# Potencia_Moway.net
KiCad netlist of a schematic drawn in Altium Designer
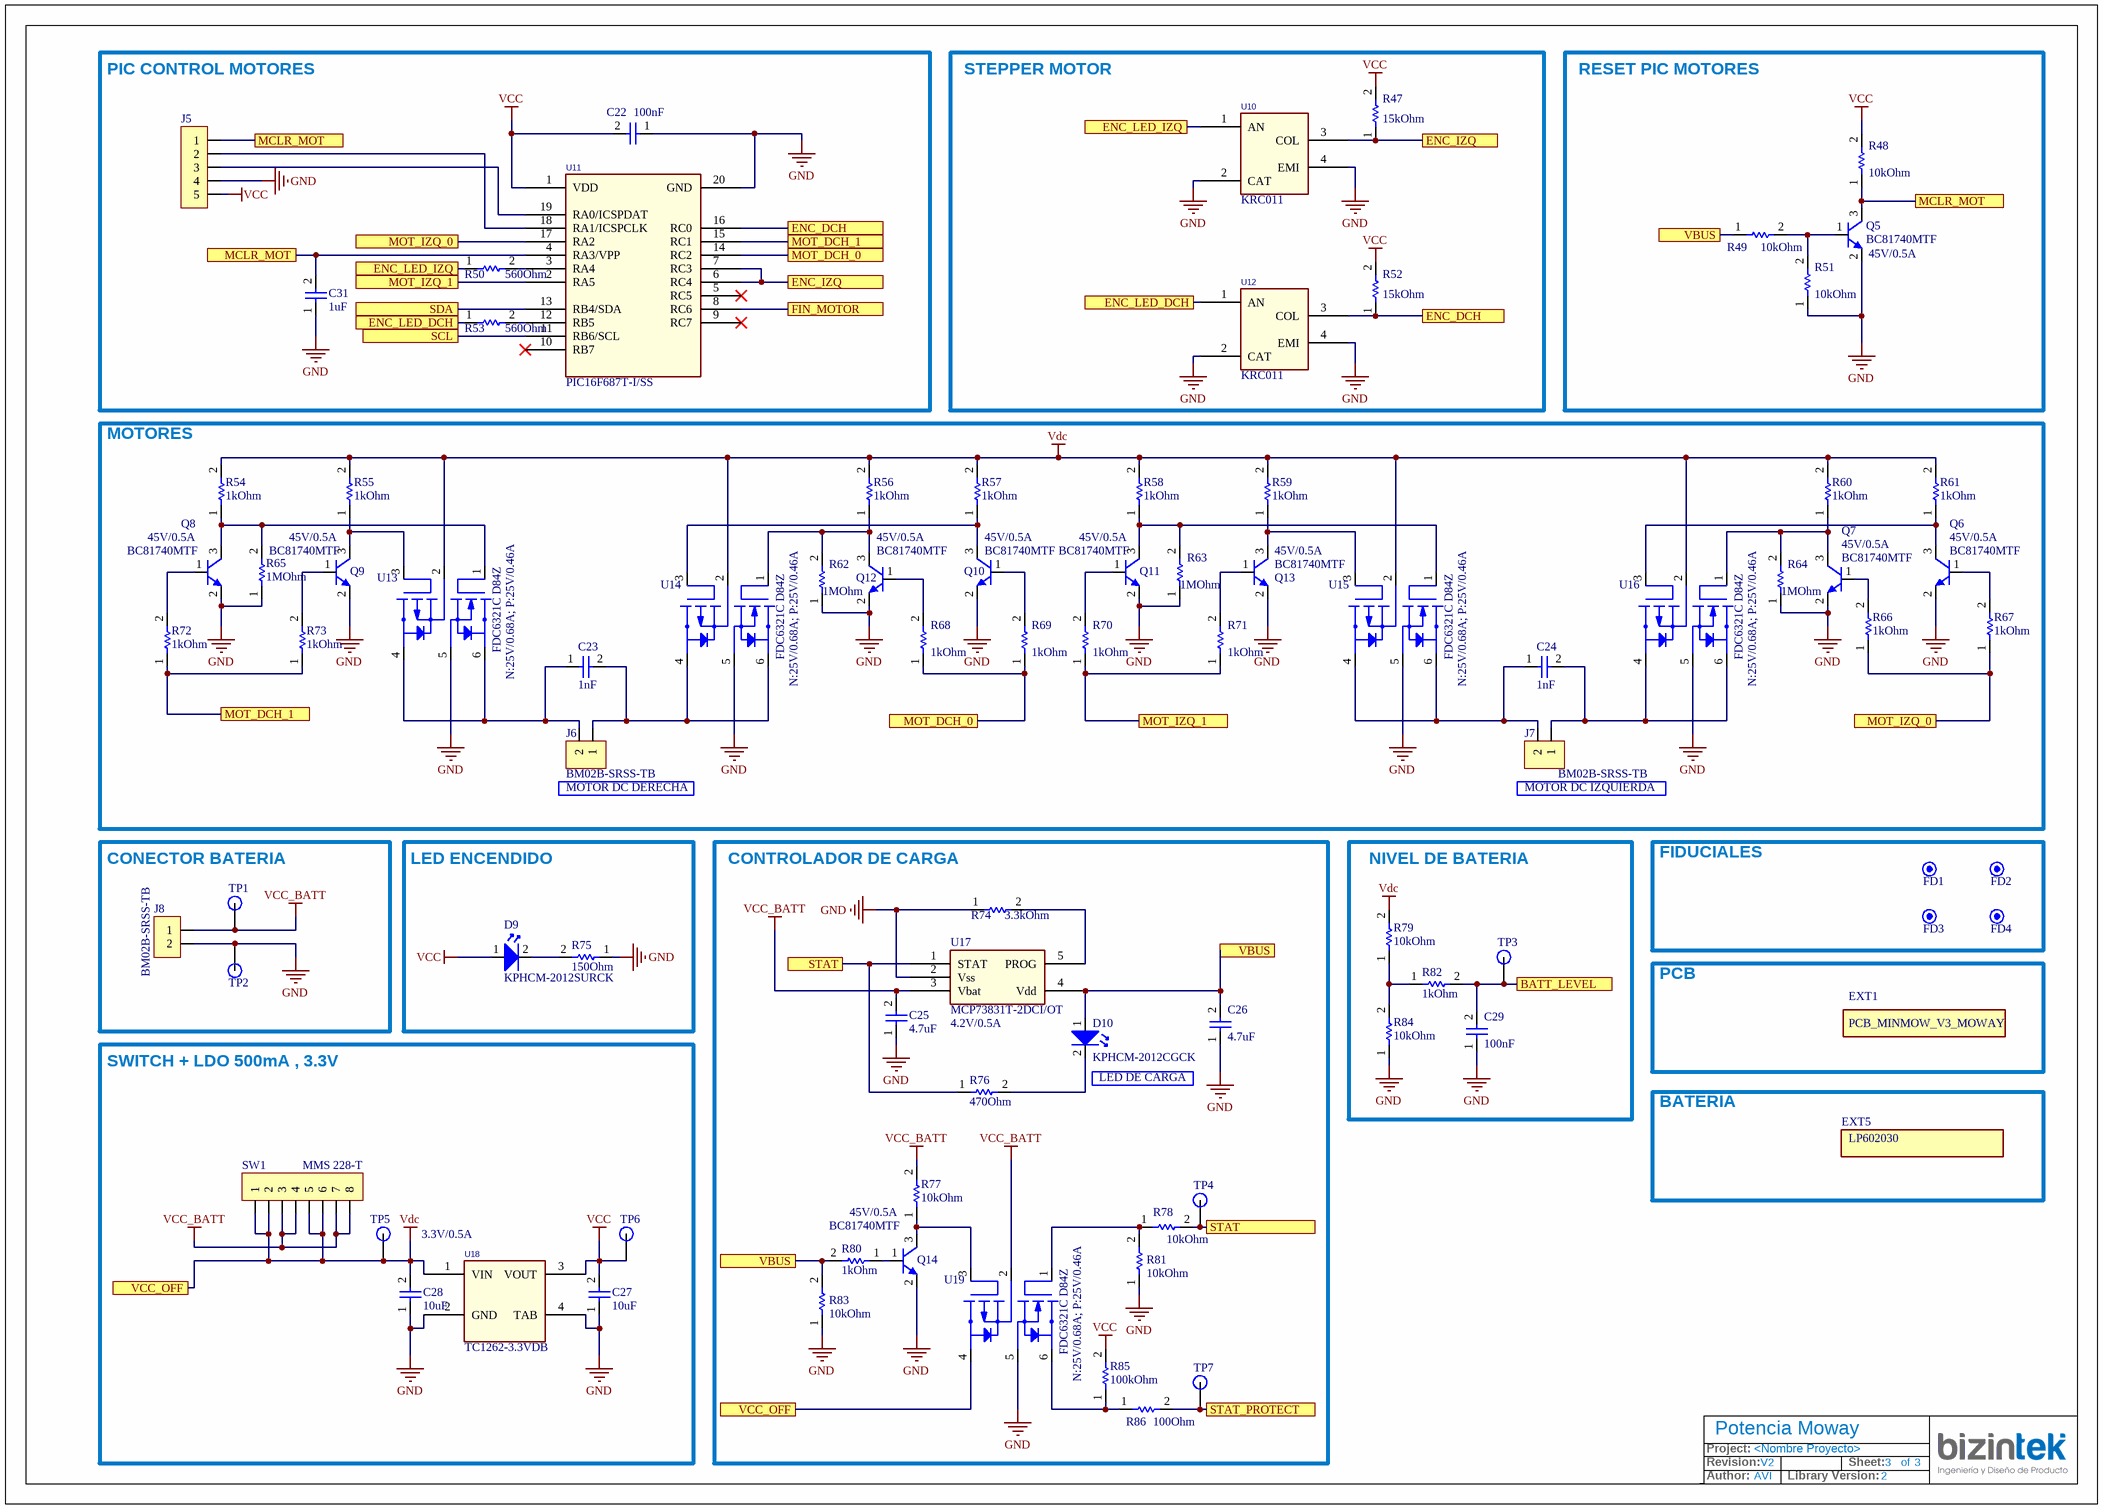
[diagram p0: Potencia_Moway.SchDoc]

(export (version "E")
  (design (tool "Eeschema 10.0.6"))
  (components
    (comp (ref "C22")
      (value "100nF")
      (footprint "C0402")
      (description "CAPACITOR SMD 0402, 100nF, 10V, X7R")
      (fields (field (name "PART NUMBER") "C100NV10X7R0402") (field (name "VOLTAGE") "10"))
      (libsource (lib "BZI_ALTIUMLIB") (part "CAPACITOR"))
    )
    (comp (ref "C23")
      (value "1nF")
      (footprint "C0402")
      (description "CAPACITOR SMD 0402, 1nF, 10V, X7R")
      (fields (field (name "PART NUMBER") "C1NV10X7R0402"))
      (libsource (lib "BZI_ALTIUMLIB") (part "CAPACITOR"))
    )
    (comp (ref "C24")
      (value "1nF")
      (footprint "C0402")
      (description "CAPACITOR SMD 0402, 1nF, 10V, X7R")
      (fields (field (name "PART NUMBER") "C1NV10X7R0402"))
      (libsource (lib "BZI_ALTIUMLIB") (part "CAPACITOR"))
    )
    (comp (ref "C25")
      (value "4.7uF")
      (footprint "C0402")
      (description "CAPACITOR SMD 0402, 4.7uF, 10V, X5R")
      (fields (field (name "PART NUMBER") "C4U7V10X5R0402") (field (name "VOLTAGE") "10"))
      (libsource (lib "BZI_ALTIUMLIB") (part "CAPACITOR"))
    )
    (comp (ref "C26")
      (value "4.7uF")
      (footprint "C0402")
      (description "CAPACITOR SMD 0402, 4.7uF, 10V, X5R")
      (fields (field (name "PART NUMBER") "C4U7V10X5R0402") (field (name "VOLTAGE") "10"))
      (libsource (lib "BZI_ALTIUMLIB") (part "CAPACITOR"))
    )
    (comp (ref "C27")
      (value "10uF")
      (footprint "C0603")
      (description "CAPACITOR SMD 0603, 10uF, 10V, X5R")
      (fields (field (name "PART NUMBER") "C10UV10X5R0603") (field (name "VOLTAGE") "10"))
      (libsource (lib "BZI_ALTIUMLIB") (part "CAPACITOR"))
    )
    (comp (ref "C28")
      (value "10uF")
      (footprint "C0603")
      (description "CAPACITOR SMD 0603, 10uF, 10V, X5R")
      (fields (field (name "PART NUMBER") "C10UV10X5R0603") (field (name "VOLTAGE") "10"))
      (libsource (lib "BZI_ALTIUMLIB") (part "CAPACITOR"))
    )
    (comp (ref "C29")
      (value "100nF")
      (footprint "C0402")
      (description "CAPACITOR SMD 0402, 100nF, 10V, X7R")
      (fields (field (name "PART NUMBER") "C100NV10X7R0402") (field (name "VOLTAGE") "10"))
      (libsource (lib "BZI_ALTIUMLIB") (part "CAPACITOR"))
    )
    (comp (ref "C31")
      (value "1uF")
      (footprint "C0402")
      (description "CAPACITOR SMD 0402, 1uF, 10V, X5R")
      (fields (field (name "PART NUMBER") "C1UV10X5R0402"))
      (libsource (lib "BZI_ALTIUMLIB") (part "CAPACITOR"))
    )
    (comp (ref "D9")
      (value "KPHCM2012SURCK")
      (footprint "LED0805")
      (description "LED, Low Power, Red, SMD, 20 mA, 1.95 V, 630 nm")
      (fields
        (field (name "MANUFACTURER PART NUMBER") "KPHCM-2012SURCK")
        (field (name "MANUFACTURER") "KINGBRIGHT")
      )
      (libsource (lib "BZI_ALTIUMLIB") (part "DIODE_LED"))
    )
    (comp (ref "D10")
      (value "KPHCM2012CGCK")
      (footprint "LED0805")
      (description "LED, Low Power, Green, SMD, 20 mA, 2.1 V, 570 nm")
      (fields
        (field (name "MANUFACTURER PART NUMBER") "KPHCM-2012CGCK")
        (field (name "MANUFACTURER") "KINGBRIGHT")
      )
      (libsource (lib "BZI_ALTIUMLIB") (part "DIODE_LED"))
    )
    (comp (ref "EXT1")
      (value "PCB_MINMOW_V3_MOWAY")
      (fields (field (name "PART NUMBER") "PCB") (field (name "MANUFACTURER") "BIZINTEK"))
      (libsource (lib "BZI_ALTIUMLIB") (part "EXTERNAL_GEN"))
    )
    (comp (ref "EXT5")
      (value "LP602030")
      (description "Li-Polymer Battery, 3.7V, 300mAh")
      (fields
        (field (name "MANUFACTURER PART NUMBER") "LP602030")
        (field (name "ALTIUM_VALUE") "3.7V/0.30Ah")
        (field (name "MANUFACTURER") "EEMB")
      )
      (libsource (lib "BZI_ALTIUMLIB") (part "EXTERNAL_GEN"))
    )
    (comp (ref "FD1")
      (value "FIDUCIAL")
      (footprint "FIDUCIAL")
      (libsource (lib "BZI_ALTIUMLIB") (part "FIDUCIAL"))
    )
    (comp (ref "FD2")
      (value "FIDUCIAL")
      (footprint "FIDUCIAL")
      (libsource (lib "BZI_ALTIUMLIB") (part "FIDUCIAL"))
    )
    (comp (ref "FD3")
      (value "FIDUCIAL")
      (footprint "FIDUCIAL")
      (libsource (lib "BZI_ALTIUMLIB") (part "FIDUCIAL"))
    )
    (comp (ref "FD4")
      (value "FIDUCIAL")
      (footprint "FIDUCIAL")
      (libsource (lib "BZI_ALTIUMLIB") (part "FIDUCIAL"))
    )
    (comp (ref "J5")
      (value "PAD_5PIN_TH_2X1MM_1.5MM_PITCH")
      (footprint "PAD_5PIN_TH_2X1MM_1.5MM_PITCH")
      (libsource (lib "BZI_ALTIUMLIB") (part "HEADER_5PIN"))
    )
    (comp (ref "J6")
      (value "BM02BSRSSTB")
      (footprint "BM02BSRSSTB_JST")
      (description "Wire-To-Board Connector, Top Entry, 1 mm, 2 Contacts, Header, SR Series, Surface Mount, 1 Rows")
      (fields (field (name "MANUFACTURER PART NUMBER") "BM02B-SRSS-TB") (field (name "MANUFACTURER") "JST"))
      (libsource (lib "BZI_ALTIUMLIB") (part "HEADER_2PIN"))
    )
    (comp (ref "J7")
      (value "BM02BSRSSTB")
      (footprint "BM02BSRSSTB_JST")
      (description "Wire-To-Board Connector, Top Entry, 1 mm, 2 Contacts, Header, SR Series, Surface Mount, 1 Rows")
      (fields (field (name "MANUFACTURER PART NUMBER") "BM02B-SRSS-TB") (field (name "MANUFACTURER") "JST"))
      (libsource (lib "BZI_ALTIUMLIB") (part "HEADER_2PIN"))
    )
    (comp (ref "J8")
      (value "BM02BSRSSTB")
      (footprint "BM02BSRSSTB_JST")
      (description "Wire-To-Board Connector, Top Entry, 1 mm, 2 Contacts, Header, SR Series, Surface Mount, 1 Rows")
      (fields (field (name "MANUFACTURER PART NUMBER") "BM02B-SRSS-TB") (field (name "MANUFACTURER") "JST"))
      (libsource (lib "BZI_ALTIUMLIB") (part "HEADER_2PIN"))
    )
    (comp (ref "Q5")
      (value "45V/0.5A")
      (footprint "SOT23_FAIRCHILD")
      (description "Bipolar (BJT) Single Transistor, NPN, 45 V, 170 MHz, 300 mW, 500 mA, 250 hFE")
      (fields
        (field (name "PART NUMBER") "BC81740MTF")
        (field (name "MANUFACTURER PART NUMBER") "BC81740MTF")
        (field (name "MANUFACTURER") "FAIRCHILD")
      )
      (libsource (lib "BZI_ALTIUMLIB") (part "BJT_NPN"))
    )
    (comp (ref "Q6")
      (value "45V/0.5A")
      (footprint "SOT23_FAIRCHILD")
      (description "Bipolar (BJT) Single Transistor, NPN, 45 V, 170 MHz, 300 mW, 500 mA, 250 hFE")
      (fields
        (field (name "PART NUMBER") "BC81740MTF")
        (field (name "MANUFACTURER PART NUMBER") "BC81740MTF")
        (field (name "MANUFACTURER") "FAIRCHILD")
      )
      (libsource (lib "BZI_ALTIUMLIB") (part "BJT_NPN"))
    )
    (comp (ref "Q7")
      (value "45V/0.5A")
      (footprint "SOT23_FAIRCHILD")
      (description "Bipolar (BJT) Single Transistor, NPN, 45 V, 170 MHz, 300 mW, 500 mA, 250 hFE")
      (fields
        (field (name "PART NUMBER") "BC81740MTF")
        (field (name "MANUFACTURER PART NUMBER") "BC81740MTF")
        (field (name "MANUFACTURER") "FAIRCHILD")
      )
      (libsource (lib "BZI_ALTIUMLIB") (part "BJT_NPN"))
    )
    (comp (ref "Q8")
      (value "45V/0.5A")
      (footprint "SOT23_FAIRCHILD")
      (description "Bipolar (BJT) Single Transistor, NPN, 45 V, 170 MHz, 300 mW, 500 mA, 250 hFE")
      (fields
        (field (name "PART NUMBER") "BC81740MTF")
        (field (name "MANUFACTURER PART NUMBER") "BC81740MTF")
        (field (name "MANUFACTURER") "FAIRCHILD")
      )
      (libsource (lib "BZI_ALTIUMLIB") (part "BJT_NPN"))
    )
    (comp (ref "Q9")
      (value "45V/0.5A")
      (footprint "SOT23_FAIRCHILD")
      (description "Bipolar (BJT) Single Transistor, NPN, 45 V, 170 MHz, 300 mW, 500 mA, 250 hFE")
      (fields
        (field (name "PART NUMBER") "BC81740MTF")
        (field (name "MANUFACTURER PART NUMBER") "BC81740MTF")
        (field (name "MANUFACTURER") "FAIRCHILD")
      )
      (libsource (lib "BZI_ALTIUMLIB") (part "BJT_NPN"))
    )
    (comp (ref "Q10")
      (value "45V/0.5A")
      (footprint "SOT23_FAIRCHILD")
      (description "Bipolar (BJT) Single Transistor, NPN, 45 V, 170 MHz, 300 mW, 500 mA, 250 hFE")
      (fields
        (field (name "PART NUMBER") "BC81740MTF")
        (field (name "MANUFACTURER PART NUMBER") "BC81740MTF")
        (field (name "MANUFACTURER") "FAIRCHILD")
      )
      (libsource (lib "BZI_ALTIUMLIB") (part "BJT_NPN"))
    )
    (comp (ref "Q11")
      (value "45V/0.5A")
      (footprint "SOT23_FAIRCHILD")
      (description "Bipolar (BJT) Single Transistor, NPN, 45 V, 170 MHz, 300 mW, 500 mA, 250 hFE")
      (fields
        (field (name "PART NUMBER") "BC81740MTF")
        (field (name "MANUFACTURER PART NUMBER") "BC81740MTF")
        (field (name "MANUFACTURER") "FAIRCHILD")
      )
      (libsource (lib "BZI_ALTIUMLIB") (part "BJT_NPN"))
    )
    (comp (ref "Q12")
      (value "45V/0.5A")
      (footprint "SOT23_FAIRCHILD")
      (description "Bipolar (BJT) Single Transistor, NPN, 45 V, 170 MHz, 300 mW, 500 mA, 250 hFE")
      (fields
        (field (name "PART NUMBER") "BC81740MTF")
        (field (name "MANUFACTURER PART NUMBER") "BC81740MTF")
        (field (name "MANUFACTURER") "FAIRCHILD")
      )
      (libsource (lib "BZI_ALTIUMLIB") (part "BJT_NPN"))
    )
    (comp (ref "Q13")
      (value "45V/0.5A")
      (footprint "SOT23_FAIRCHILD")
      (description "Bipolar (BJT) Single Transistor, NPN, 45 V, 170 MHz, 300 mW, 500 mA, 250 hFE")
      (fields
        (field (name "PART NUMBER") "BC81740MTF")
        (field (name "MANUFACTURER PART NUMBER") "BC81740MTF")
        (field (name "MANUFACTURER") "FAIRCHILD")
      )
      (libsource (lib "BZI_ALTIUMLIB") (part "BJT_NPN"))
    )
    (comp (ref "Q14")
      (value "45V/0.5A")
      (footprint "SOT23_FAIRCHILD")
      (description "Bipolar (BJT) Single Transistor, NPN, 45 V, 170 MHz, 300 mW, 500 mA, 250 hFE")
      (fields
        (field (name "PART NUMBER") "BC81740MTF")
        (field (name "MANUFACTURER PART NUMBER") "BC81740MTF")
        (field (name "MANUFACTURER") "FAIRCHILD")
      )
      (libsource (lib "BZI_ALTIUMLIB") (part "BJT_NPN"))
    )
    (comp (ref "R47")
      (value "15kOhm")
      (footprint "R0402")
      (description "RESISTOR SMD 0402, 15kOhm, 1%")
      (fields (field (name "PART NUMBER") "R15KT10402") (field (name "TOLERANCE") "1"))
      (libsource (lib "BZI_ALTIUMLIB") (part "RESISTOR"))
    )
    (comp (ref "R48")
      (value "10kOhm")
      (footprint "R0402")
      (description "RESISTOR SMD 0402, 10kOhm, 1%")
      (fields (field (name "PART NUMBER") "R10KT10402") (field (name "TOLERANCE") "1"))
      (libsource (lib "BZI_ALTIUMLIB") (part "RESISTOR"))
    )
    (comp (ref "R49")
      (value "10kOhm")
      (footprint "R0402")
      (description "RESISTOR SMD 0402, 10kOhm, 1%")
      (fields (field (name "PART NUMBER") "R10KT10402") (field (name "TOLERANCE") "1"))
      (libsource (lib "BZI_ALTIUMLIB") (part "RESISTOR"))
    )
    (comp (ref "R50")
      (value "560Ohm")
      (footprint "R0402")
      (description "RESISTOR SMD 0402, 560Ohm, 1%")
      (fields (field (name "PART NUMBER") "R560T10402") (field (name "TOLERANCE") "1"))
      (libsource (lib "BZI_ALTIUMLIB") (part "RESISTOR"))
    )
    (comp (ref "R51")
      (value "10kOhm")
      (footprint "R0402")
      (description "RESISTOR SMD 0402, 10kOhm, 1%")
      (fields (field (name "PART NUMBER") "R10KT10402") (field (name "TOLERANCE") "1"))
      (libsource (lib "BZI_ALTIUMLIB") (part "RESISTOR"))
    )
    (comp (ref "R52")
      (value "15kOhm")
      (footprint "R0402")
      (description "RESISTOR SMD 0402, 15kOhm, 1%")
      (fields (field (name "PART NUMBER") "R15KT10402") (field (name "TOLERANCE") "1"))
      (libsource (lib "BZI_ALTIUMLIB") (part "RESISTOR"))
    )
    (comp (ref "R53")
      (value "560Ohm")
      (footprint "R0402")
      (description "RESISTOR SMD 0402, 560Ohm, 1%")
      (fields (field (name "PART NUMBER") "R560T10402") (field (name "TOLERANCE") "1"))
      (libsource (lib "BZI_ALTIUMLIB") (part "RESISTOR"))
    )
    (comp (ref "R54")
      (value "1kOhm")
      (footprint "R0402")
      (description "RESISTOR SMD 0402, 1kOhm, 1%")
      (fields (field (name "PART NUMBER") "R1KT10402") (field (name "TOLERANCE") "1"))
      (libsource (lib "BZI_ALTIUMLIB") (part "RESISTOR"))
    )
    (comp (ref "R55")
      (value "1kOhm")
      (footprint "R0402")
      (description "RESISTOR SMD 0402, 1kOhm, 1%")
      (fields (field (name "PART NUMBER") "R1KT10402") (field (name "TOLERANCE") "1"))
      (libsource (lib "BZI_ALTIUMLIB") (part "RESISTOR"))
    )
    (comp (ref "R56")
      (value "1kOhm")
      (footprint "R0402")
      (description "RESISTOR SMD 0402, 1kOhm, 1%")
      (fields (field (name "PART NUMBER") "R1KT10402") (field (name "TOLERANCE") "1"))
      (libsource (lib "BZI_ALTIUMLIB") (part "RESISTOR"))
    )
    (comp (ref "R57")
      (value "1kOhm")
      (footprint "R0402")
      (description "RESISTOR SMD 0402, 1kOhm, 1%")
      (fields (field (name "PART NUMBER") "R1KT10402") (field (name "TOLERANCE") "1"))
      (libsource (lib "BZI_ALTIUMLIB") (part "RESISTOR"))
    )
    (comp (ref "R58")
      (value "1kOhm")
      (footprint "R0402")
      (description "RESISTOR SMD 0402, 1kOhm, 1%")
      (fields (field (name "PART NUMBER") "R1KT10402") (field (name "TOLERANCE") "1"))
      (libsource (lib "BZI_ALTIUMLIB") (part "RESISTOR"))
    )
    (comp (ref "R59")
      (value "1kOhm")
      (footprint "R0402")
      (description "RESISTOR SMD 0402, 1kOhm, 1%")
      (fields (field (name "PART NUMBER") "R1KT10402") (field (name "TOLERANCE") "1"))
      (libsource (lib "BZI_ALTIUMLIB") (part "RESISTOR"))
    )
    (comp (ref "R60")
      (value "1kOhm")
      (footprint "R0402")
      (description "RESISTOR SMD 0402, 1kOhm, 1%")
      (fields (field (name "PART NUMBER") "R1KT10402") (field (name "TOLERANCE") "1"))
      (libsource (lib "BZI_ALTIUMLIB") (part "RESISTOR"))
    )
    (comp (ref "R61")
      (value "1kOhm")
      (footprint "R0402")
      (description "RESISTOR SMD 0402, 1kOhm, 1%")
      (fields (field (name "PART NUMBER") "R1KT10402") (field (name "TOLERANCE") "1"))
      (libsource (lib "BZI_ALTIUMLIB") (part "RESISTOR"))
    )
    (comp (ref "R62")
      (value "1MOhm")
      (footprint "R0402")
      (description "RESISTOR SMD 0402, 1MOhm, 1%")
      (fields (field (name "PART NUMBER") "R1MT10402") (field (name "TOLERANCE") "1"))
      (libsource (lib "BZI_ALTIUMLIB") (part "RESISTOR"))
    )
    (comp (ref "R63")
      (value "1MOhm")
      (footprint "R0402")
      (description "RESISTOR SMD 0402, 1MOhm, 1%")
      (fields (field (name "PART NUMBER") "R1MT10402") (field (name "TOLERANCE") "1"))
      (libsource (lib "BZI_ALTIUMLIB") (part "RESISTOR"))
    )
    (comp (ref "R64")
      (value "1MOhm")
      (footprint "R0402")
      (description "RESISTOR SMD 0402, 1MOhm, 1%")
      (fields (field (name "PART NUMBER") "R1MT10402") (field (name "TOLERANCE") "1"))
      (libsource (lib "BZI_ALTIUMLIB") (part "RESISTOR"))
    )
    (comp (ref "R65")
      (value "1MOhm")
      (footprint "R0402")
      (description "RESISTOR SMD 0402, 1MOhm, 1%")
      (fields (field (name "PART NUMBER") "R1MT10402") (field (name "TOLERANCE") "1"))
      (libsource (lib "BZI_ALTIUMLIB") (part "RESISTOR"))
    )
    (comp (ref "R66")
      (value "1kOhm")
      (footprint "R0402")
      (description "RESISTOR SMD 0402, 1kOhm, 1%")
      (fields (field (name "PART NUMBER") "R1KT10402") (field (name "TOLERANCE") "1"))
      (libsource (lib "BZI_ALTIUMLIB") (part "RESISTOR"))
    )
    (comp (ref "R67")
      (value "1kOhm")
      (footprint "R0402")
      (description "RESISTOR SMD 0402, 1kOhm, 1%")
      (fields (field (name "PART NUMBER") "R1KT10402") (field (name "TOLERANCE") "1"))
      (libsource (lib "BZI_ALTIUMLIB") (part "RESISTOR"))
    )
    (comp (ref "R68")
      (value "1kOhm")
      (footprint "R0402")
      (description "RESISTOR SMD 0402, 1kOhm, 1%")
      (fields (field (name "PART NUMBER") "R1KT10402") (field (name "TOLERANCE") "1"))
      (libsource (lib "BZI_ALTIUMLIB") (part "RESISTOR"))
    )
    (comp (ref "R69")
      (value "1kOhm")
      (footprint "R0402")
      (description "RESISTOR SMD 0402, 1kOhm, 1%")
      (fields (field (name "PART NUMBER") "R1KT10402") (field (name "TOLERANCE") "1"))
      (libsource (lib "BZI_ALTIUMLIB") (part "RESISTOR"))
    )
    (comp (ref "R70")
      (value "1kOhm")
      (footprint "R0402")
      (description "RESISTOR SMD 0402, 1kOhm, 1%")
      (fields (field (name "PART NUMBER") "R1KT10402") (field (name "TOLERANCE") "1"))
      (libsource (lib "BZI_ALTIUMLIB") (part "RESISTOR"))
    )
    (comp (ref "R71")
      (value "1kOhm")
      (footprint "R0402")
      (description "RESISTOR SMD 0402, 1kOhm, 1%")
      (fields (field (name "PART NUMBER") "R1KT10402") (field (name "TOLERANCE") "1"))
      (libsource (lib "BZI_ALTIUMLIB") (part "RESISTOR"))
    )
    (comp (ref "R72")
      (value "1kOhm")
      (footprint "R0402")
      (description "RESISTOR SMD 0402, 1kOhm, 1%")
      (fields (field (name "PART NUMBER") "R1KT10402") (field (name "TOLERANCE") "1"))
      (libsource (lib "BZI_ALTIUMLIB") (part "RESISTOR"))
    )
    (comp (ref "R73")
      (value "1kOhm")
      (footprint "R0402")
      (description "RESISTOR SMD 0402, 1kOhm, 1%")
      (fields (field (name "PART NUMBER") "R1KT10402") (field (name "TOLERANCE") "1"))
      (libsource (lib "BZI_ALTIUMLIB") (part "RESISTOR"))
    )
    (comp (ref "R74")
      (value "3.3kOhm")
      (footprint "R0402")
      (description "RESISTOR SMD 0402, 3.3kOhm, 1%")
      (fields (field (name "PART NUMBER") "R3K3T10402") (field (name "TOLERANCE") "1"))
      (libsource (lib "BZI_ALTIUMLIB") (part "RESISTOR"))
    )
    (comp (ref "R75")
      (value "150Ohm")
      (footprint "R0402")
      (description "RESISTOR SMD 0402, 150Ohm, 1%")
      (fields (field (name "PART NUMBER") "R150T10402") (field (name "TOLERANCE") "1"))
      (libsource (lib "BZI_ALTIUMLIB") (part "RESISTOR"))
    )
    (comp (ref "R76")
      (value "470Ohm")
      (footprint "R0402")
      (description "RESISTOR SMD 0402, 470Ohm, 1%")
      (fields (field (name "PART NUMBER") "R470T10402") (field (name "TOLERANCE") "1"))
      (libsource (lib "BZI_ALTIUMLIB") (part "RESISTOR"))
    )
    (comp (ref "R77")
      (value "10kOhm")
      (footprint "R0402")
      (description "RESISTOR SMD 0402, 10kOhm, 1%")
      (fields (field (name "PART NUMBER") "R10KT10402") (field (name "TOLERANCE") "1"))
      (libsource (lib "BZI_ALTIUMLIB") (part "RESISTOR"))
    )
    (comp (ref "R78")
      (value "10kOhm")
      (footprint "R0402")
      (description "RESISTOR SMD 0402, 10kOhm, 1%")
      (fields (field (name "PART NUMBER") "R10KT10402") (field (name "TOLERANCE") "1"))
      (libsource (lib "BZI_ALTIUMLIB") (part "RESISTOR"))
    )
    (comp (ref "R79")
      (value "10kOhm")
      (footprint "R0402")
      (description "RESISTOR SMD 0402, 10kOhm, 1%")
      (fields (field (name "PART NUMBER") "R10KT10402") (field (name "TOLERANCE") "1"))
      (libsource (lib "BZI_ALTIUMLIB") (part "RESISTOR"))
    )
    (comp (ref "R80")
      (value "1kOhm")
      (footprint "R0402")
      (description "RESISTOR SMD 0402, 1kOhm, 1%")
      (fields (field (name "PART NUMBER") "R1KT10402") (field (name "TOLERANCE") "1"))
      (libsource (lib "BZI_ALTIUMLIB") (part "RESISTOR"))
    )
    (comp (ref "R81")
      (value "10kOhm")
      (footprint "R0402")
      (description "RESISTOR SMD 0402, 10kOhm, 1%")
      (fields (field (name "PART NUMBER") "R10KT10402") (field (name "TOLERANCE") "1"))
      (libsource (lib "BZI_ALTIUMLIB") (part "RESISTOR"))
    )
    (comp (ref "R82")
      (value "1kOhm")
      (footprint "R0402")
      (description "RESISTOR SMD 0402, 1kOhm, 1%")
      (fields (field (name "PART NUMBER") "R1KT10402") (field (name "TOLERANCE") "1"))
      (libsource (lib "BZI_ALTIUMLIB") (part "RESISTOR"))
    )
    (comp (ref "R83")
      (value "10kOhm")
      (footprint "R0402")
      (description "RESISTOR SMD 0402, 10kOhm, 1%")
      (fields (field (name "PART NUMBER") "R10KT10402") (field (name "TOLERANCE") "1"))
      (libsource (lib "BZI_ALTIUMLIB") (part "RESISTOR"))
    )
    (comp (ref "R84")
      (value "10kOhm")
      (footprint "R0402")
      (description "RESISTOR SMD 0402, 10kOhm, 1%")
      (fields (field (name "PART NUMBER") "R10KT10402") (field (name "TOLERANCE") "1"))
      (libsource (lib "BZI_ALTIUMLIB") (part "RESISTOR"))
    )
    (comp (ref "R85")
      (value "100kOhm")
      (footprint "R0402")
      (description "RESISTOR SMD 0402, 100kOhm, 1%")
      (fields (field (name "PART NUMBER") "R100KT10402") (field (name "TOLERANCE") "1"))
      (libsource (lib "BZI_ALTIUMLIB") (part "RESISTOR"))
    )
    (comp (ref "R86")
      (value "100Ohm")
      (footprint "R0402")
      (description "RESISTOR SMD 0402, 100Ohm, 1%")
      (fields (field (name "PART NUMBER") "R100T10402") (field (name "TOLERANCE") "1"))
      (libsource (lib "BZI_ALTIUMLIB") (part "RESISTOR"))
    )
    (comp (ref "SW1")
      (value "MMS228T")
      (footprint "MMS228T")
      (description "Slide Switch, DPDT, On-On, SMD, 300 mA")
      (fields (field (name "MANUFACTURER PART NUMBER") "MMS 228-T") (field (name "MANUFACTURER") "KNITTER"))
      (libsource (lib "BZI_ALTIUMLIB") (part "HEADER_8PIN"))
    )
    (comp (ref "TP1")
      (value "TEST_POINT_1MM")
      (footprint "TEST_POINT_1MM")
      (libsource (lib "BZI_ALTIUMLIB") (part "TEST_POINT"))
    )
    (comp (ref "TP2")
      (value "TEST_POINT_1MM")
      (footprint "TEST_POINT_1MM")
      (libsource (lib "BZI_ALTIUMLIB") (part "TEST_POINT"))
    )
    (comp (ref "TP3")
      (value "TEST_POINT_1MM")
      (footprint "TEST_POINT_1MM")
      (libsource (lib "BZI_ALTIUMLIB") (part "TEST_POINT"))
    )
    (comp (ref "TP4")
      (value "TEST_POINT_1MM")
      (footprint "TEST_POINT_1MM")
      (libsource (lib "BZI_ALTIUMLIB") (part "TEST_POINT"))
    )
    (comp (ref "TP5")
      (value "TEST_POINT_1MM")
      (footprint "TEST_POINT_1MM")
      (libsource (lib "BZI_ALTIUMLIB") (part "TEST_POINT"))
    )
    (comp (ref "TP6")
      (value "TEST_POINT_1MM")
      (footprint "TEST_POINT_1MM")
      (libsource (lib "BZI_ALTIUMLIB") (part "TEST_POINT"))
    )
    (comp (ref "TP7")
      (value "TEST_POINT_1MM")
      (footprint "TEST_POINT_1MM")
      (libsource (lib "BZI_ALTIUMLIB") (part "TEST_POINT"))
    )
    (comp (ref "U10")
      (value "KRC011")
      (footprint "KRC011")
      (description "High Sensitivity Photointerrupter")
      (fields (field (name "MANUFACTURER PART NUMBER") "KRC011") (field (name "MANUFACTURER") "KINGBRIGHT"))
      (libsource (lib "BZI_ALTIUMLIB") (part "KRC011"))
    )
    (comp (ref "U11")
      (value "PIC16F687TISS")
      (footprint "SSOP20_MCP")
      (description "20 PIN FLASH 8-Bit CMOS MCU")
      (fields
        (field (name "MANUFACTURER PART NUMBER") "PIC16F687T-I/SS")
        (field (name "MANUFACTURER") "MICROCHIP")
      )
      (libsource (lib "BZI_ALTIUMLIB") (part "PIC16F687TISS"))
    )
    (comp (ref "U12")
      (value "KRC011")
      (footprint "KRC011")
      (description "High Sensitivity Photointerrupter")
      (fields (field (name "MANUFACTURER PART NUMBER") "KRC011") (field (name "MANUFACTURER") "KINGBRIGHT"))
      (libsource (lib "BZI_ALTIUMLIB") (part "KRC011"))
    )
    (comp (ref "U13")
      (value "N:25V/0.68A; P:25V/0.46A")
      (footprint "SUPERSOT6_ONSEMI")
      (description "Dual MOSFET, N and P Channel, 460 mA, 25 V, 0.33 ohm, 4.5 V, 800 mV")
      (fields
        (field (name "PART NUMBER") "FDC6321CD84Z")
        (field (name "MANUFACTURER PART NUMBER") "FDC6321C D84Z")
        (field (name "MANUFACTURER") "FAIRCHILD")
      )
      (libsource (lib "BZI_ALTIUMLIB") (part "MOSFET_P_N"))
    )
    (comp (ref "U14")
      (value "N:25V/0.68A; P:25V/0.46A")
      (footprint "SUPERSOT6_ONSEMI")
      (description "Dual MOSFET, N and P Channel, 460 mA, 25 V, 0.33 ohm, 4.5 V, 800 mV")
      (fields
        (field (name "PART NUMBER") "FDC6321CD84Z")
        (field (name "MANUFACTURER PART NUMBER") "FDC6321C D84Z")
        (field (name "MANUFACTURER") "FAIRCHILD")
      )
      (libsource (lib "BZI_ALTIUMLIB") (part "MOSFET_P_N"))
    )
    (comp (ref "U15")
      (value "N:25V/0.68A; P:25V/0.46A")
      (footprint "SUPERSOT6_ONSEMI")
      (description "Dual MOSFET, N and P Channel, 460 mA, 25 V, 0.33 ohm, 4.5 V, 800 mV")
      (fields
        (field (name "PART NUMBER") "FDC6321CD84Z")
        (field (name "MANUFACTURER PART NUMBER") "FDC6321C D84Z")
        (field (name "MANUFACTURER") "FAIRCHILD")
      )
      (libsource (lib "BZI_ALTIUMLIB") (part "MOSFET_P_N"))
    )
    (comp (ref "U16")
      (value "N:25V/0.68A; P:25V/0.46A")
      (footprint "SUPERSOT6_ONSEMI")
      (description "Dual MOSFET, N and P Channel, 460 mA, 25 V, 0.33 ohm, 4.5 V, 800 mV")
      (fields
        (field (name "PART NUMBER") "FDC6321CD84Z")
        (field (name "MANUFACTURER PART NUMBER") "FDC6321C D84Z")
        (field (name "MANUFACTURER") "FAIRCHILD")
      )
      (libsource (lib "BZI_ALTIUMLIB") (part "MOSFET_P_N"))
    )
    (comp (ref "U17")
      (value "4.2V/0.5A")
      (footprint "SOT23-5_MCP")
      (description "Battery Charger for 1 Cell of Li-Ion, Li-Pol battery, 6V input, 4.2V / 500mA charge")
      (fields
        (field (name "PART NUMBER") "MCP73831T2DCIOT")
        (field (name "MANUFACTURER PART NUMBER") "MCP73831T-2DCI/OT")
        (field (name "MANUFACTURER") "MICROCHIP")
      )
      (libsource (lib "BZI_ALTIUMLIB") (part "MCP73831T2DCIOT"))
    )
    (comp (ref "U18")
      (value "3.3V/0.5A")
      (footprint "SOT223_MCP")
      (description "500mA Fixed Output CMOS LDO. 6V Vin, 3.3 Vout, 0.5Aout")
      (fields
        (field (name "PART NUMBER") "TC126233VDB")
        (field (name "MANUFACTURER PART NUMBER") "TC1262-3.3VDB")
        (field (name "MANUFACTURER") "MICROCHIP")
      )
      (libsource (lib "BZI_ALTIUMLIB") (part "TC126233VDB"))
    )
    (comp (ref "U19")
      (value "N:25V/0.68A; P:25V/0.46A")
      (footprint "SUPERSOT6_ONSEMI")
      (description "Dual MOSFET, N and P Channel, 460 mA, 25 V, 0.33 ohm, 4.5 V, 800 mV")
      (fields
        (field (name "PART NUMBER") "FDC6321CD84Z")
        (field (name "MANUFACTURER PART NUMBER") "FDC6321C D84Z")
        (field (name "MANUFACTURER") "FAIRCHILD")
      )
      (libsource (lib "BZI_ALTIUMLIB") (part "MOSFET_P_N"))
    )
  )
  (nets
    (net (code "1") (name "/BATT_LEVEL") (class "Default")
      (node (ref "C29") (pin "2") (pinfunction "2_2") (pintype "passive"))
      (node (ref "R82") (pin "2") (pinfunction "2_2") (pintype "passive"))
      (node (ref "TP3") (pin "1") (pinfunction "1_1") (pintype "passive"))
    )
    (net (code "2") (name "/ENC_DCH") (class "Default")
      (node (ref "R52") (pin "1") (pinfunction "1_1") (pintype "passive"))
      (node (ref "U11") (pin "16") (pinfunction "RC0_16") (pintype "passive"))
      (node (ref "U12") (pin "3") (pinfunction "COL_3") (pintype "passive"))
    )
    (net (code "3") (name "/ENC_IZQ") (class "Default")
      (node (ref "R47") (pin "1") (pinfunction "1_1") (pintype "passive"))
      (node (ref "U10") (pin "3") (pinfunction "COL_3") (pintype "passive"))
      (node (ref "U11") (pin "6") (pinfunction "RC4_6") (pintype "passive"))
      (node (ref "U11") (pin "7") (pinfunction "RC3_7") (pintype "passive"))
    )
    (net (code "4") (name "/ENC_LED_DCH") (class "Default")
      (node (ref "R53") (pin "1") (pinfunction "1_1") (pintype "passive"))
      (node (ref "U12") (pin "1") (pinfunction "AN_1") (pintype "passive"))
    )
    (net (code "5") (name "/ENC_LED_IZQ") (class "Default")
      (node (ref "R50") (pin "1") (pinfunction "1_1") (pintype "passive"))
      (node (ref "U10") (pin "1") (pinfunction "AN_1") (pintype "passive"))
    )
    (net (code "6") (name "/FIN_MOTOR") (class "Default")
      (node (ref "U11") (pin "8") (pinfunction "RC6_8") (pintype "passive"))
    )
    (net (code "7") (name "/MCLR_MOT") (class "Default")
      (node (ref "C31") (pin "2") (pinfunction "2_2") (pintype "passive"))
      (node (ref "J5") (pin "1") (pinfunction "1_1") (pintype "passive"))
      (node (ref "Q5") (pin "3") (pinfunction "C_3") (pintype "passive"))
      (node (ref "R48") (pin "1") (pinfunction "1_1") (pintype "passive"))
      (node (ref "U11") (pin "4") (pinfunction "RA3/VPP_4") (pintype "passive"))
    )
    (net (code "8") (name "/MOT_DCH_0") (class "Default")
      (node (ref "R68") (pin "1") (pinfunction "1_1") (pintype "passive"))
      (node (ref "R69") (pin "1") (pinfunction "1_1") (pintype "passive"))
      (node (ref "U11") (pin "14") (pinfunction "RC2_14") (pintype "passive"))
    )
    (net (code "9") (name "/MOT_DCH_1") (class "Default")
      (node (ref "R72") (pin "1") (pinfunction "1_1") (pintype "passive"))
      (node (ref "R73") (pin "1") (pinfunction "1_1") (pintype "passive"))
      (node (ref "U11") (pin "15") (pinfunction "RC1_15") (pintype "passive"))
    )
    (net (code "10") (name "/MOT_IZQ_0") (class "Default")
      (node (ref "R66") (pin "1") (pinfunction "1_1") (pintype "passive"))
      (node (ref "R67") (pin "1") (pinfunction "1_1") (pintype "passive"))
      (node (ref "U11") (pin "17") (pinfunction "RA2_17") (pintype "passive"))
    )
    (net (code "11") (name "/MOT_IZQ_1") (class "Default")
      (node (ref "R70") (pin "1") (pinfunction "1_1") (pintype "passive"))
      (node (ref "R71") (pin "1") (pinfunction "1_1") (pintype "passive"))
      (node (ref "U11") (pin "2") (pinfunction "RA5_2") (pintype "passive"))
    )
    (net (code "12") (name "/SCL") (class "Default")
      (node (ref "U11") (pin "11") (pinfunction "RB6/SCL_11") (pintype "passive"))
    )
    (net (code "13") (name "/SDA") (class "Default")
      (node (ref "U11") (pin "13") (pinfunction "RB4/SDA_13") (pintype "passive"))
    )
    (net (code "14") (name "/STAT") (class "Default")
      (node (ref "R76") (pin "1") (pinfunction "1_1") (pintype "passive"))
      (node (ref "R78") (pin "2") (pinfunction "2_2") (pintype "passive"))
      (node (ref "TP4") (pin "1") (pinfunction "1_1") (pintype "passive"))
      (node (ref "U17") (pin "1") (pinfunction "STAT_1") (pintype "passive"))
    )
    (net (code "15") (name "/STAT_PROTECT") (class "Default")
      (node (ref "R86") (pin "2") (pinfunction "2_2") (pintype "passive"))
      (node (ref "TP7") (pin "1") (pinfunction "1_1") (pintype "passive"))
    )
    (net (code "16") (name "/VBUS") (class "Default")
      (node (ref "C26") (pin "2") (pinfunction "2_2") (pintype "passive"))
      (node (ref "D10") (pin "1") (pinfunction "A_1") (pintype "passive"))
      (node (ref "R49") (pin "1") (pinfunction "1_1") (pintype "passive"))
      (node (ref "R80") (pin "2") (pinfunction "2_2") (pintype "passive"))
      (node (ref "R83") (pin "2") (pinfunction "2_2") (pintype "passive"))
      (node (ref "U17") (pin "4") (pinfunction "Vdd_4") (pintype "passive"))
    )
    (net (code "17") (name "GND") (class "Default")
      (node (ref "C22") (pin "1") (pinfunction "1_1") (pintype "passive"))
      (node (ref "C25") (pin "1") (pinfunction "1_1") (pintype "passive"))
      (node (ref "C26") (pin "1") (pinfunction "1_1") (pintype "passive"))
      (node (ref "C27") (pin "1") (pinfunction "1_1") (pintype "passive"))
      (node (ref "C28") (pin "1") (pinfunction "1_1") (pintype "passive"))
      (node (ref "C29") (pin "1") (pinfunction "1_1") (pintype "passive"))
      (node (ref "C31") (pin "1") (pinfunction "1_1") (pintype "passive"))
      (node (ref "J5") (pin "4") (pinfunction "4_4") (pintype "passive"))
      (node (ref "J8") (pin "2") (pinfunction "2_2") (pintype "passive"))
      (node (ref "Q10") (pin "2") (pinfunction "E_2") (pintype "passive"))
      (node (ref "Q11") (pin "2") (pinfunction "E_2") (pintype "passive"))
      (node (ref "Q12") (pin "2") (pinfunction "E_2") (pintype "passive"))
      (node (ref "Q13") (pin "2") (pinfunction "E_2") (pintype "passive"))
      (node (ref "Q14") (pin "2") (pinfunction "E_2") (pintype "passive"))
      (node (ref "Q5") (pin "2") (pinfunction "E_2") (pintype "passive"))
      (node (ref "Q6") (pin "2") (pinfunction "E_2") (pintype "passive"))
      (node (ref "Q7") (pin "2") (pinfunction "E_2") (pintype "passive"))
      (node (ref "Q8") (pin "2") (pinfunction "E_2") (pintype "passive"))
      (node (ref "Q9") (pin "2") (pinfunction "E_2") (pintype "passive"))
      (node (ref "R51") (pin "1") (pinfunction "1_1") (pintype "passive"))
      (node (ref "R62") (pin "1") (pinfunction "1_1") (pintype "passive"))
      (node (ref "R63") (pin "1") (pinfunction "1_1") (pintype "passive"))
      (node (ref "R64") (pin "1") (pinfunction "1_1") (pintype "passive"))
      (node (ref "R65") (pin "1") (pinfunction "1_1") (pintype "passive"))
      (node (ref "R74") (pin "1") (pinfunction "1_1") (pintype "passive"))
      (node (ref "R75") (pin "1") (pinfunction "1_1") (pintype "passive"))
      (node (ref "R81") (pin "1") (pinfunction "1_1") (pintype "passive"))
      (node (ref "R83") (pin "1") (pinfunction "1_1") (pintype "passive"))
      (node (ref "R84") (pin "1") (pinfunction "1_1") (pintype "passive"))
      (node (ref "TP2") (pin "1") (pinfunction "1_1") (pintype "passive"))
      (node (ref "U10") (pin "2") (pinfunction "CAT_2") (pintype "passive"))
      (node (ref "U10") (pin "4") (pinfunction "EMI_4") (pintype "passive"))
      (node (ref "U11") (pin "20") (pinfunction "GND_20") (pintype "passive"))
      (node (ref "U12") (pin "2") (pinfunction "CAT_2") (pintype "passive"))
      (node (ref "U12") (pin "4") (pinfunction "EMI_4") (pintype "passive"))
      (node (ref "U13") (pin "5") (pinfunction "S2_5") (pintype "passive"))
      (node (ref "U14") (pin "5") (pinfunction "S2_5") (pintype "passive"))
      (node (ref "U15") (pin "5") (pinfunction "S2_5") (pintype "passive"))
      (node (ref "U16") (pin "5") (pinfunction "S2_5") (pintype "passive"))
      (node (ref "U17") (pin "2") (pinfunction "Vss_2") (pintype "passive"))
      (node (ref "U18") (pin "2") (pinfunction "GND_2") (pintype "passive"))
      (node (ref "U18") (pin "4") (pinfunction "TAB_4") (pintype "passive"))
      (node (ref "U19") (pin "5") (pinfunction "S2_5") (pintype "passive"))
    )
    (net (code "18") (name "Net-(D9-K)") (class "Default")
      (node (ref "D9") (pin "2") (pinfunction "K_2") (pintype "passive"))
      (node (ref "R75") (pin "2") (pinfunction "2_2") (pintype "passive"))
    )
    (net (code "19") (name "Net-(D10-K)") (class "Default")
      (node (ref "D10") (pin "2") (pinfunction "K_2") (pintype "passive"))
      (node (ref "R76") (pin "2") (pinfunction "2_2") (pintype "passive"))
    )
    (net (code "20") (name "Net-(Q5-B)") (class "Default")
      (node (ref "Q5") (pin "1") (pinfunction "B_1") (pintype "passive"))
      (node (ref "R49") (pin "2") (pinfunction "2_2") (pintype "passive"))
      (node (ref "R51") (pin "2") (pinfunction "2_2") (pintype "passive"))
    )
    (net (code "21") (name "Net-(Q6-B)") (class "Default")
      (node (ref "Q6") (pin "1") (pinfunction "B_1") (pintype "passive"))
      (node (ref "R67") (pin "2") (pinfunction "2_2") (pintype "passive"))
    )
    (net (code "22") (name "Net-(Q6-C)") (class "Default")
      (node (ref "Q6") (pin "3") (pinfunction "C_3") (pintype "passive"))
      (node (ref "R61") (pin "1") (pinfunction "1_1") (pintype "passive"))
      (node (ref "U16") (pin "3") (pinfunction "G1_3") (pintype "passive"))
    )
    (net (code "23") (name "Net-(Q7-B)") (class "Default")
      (node (ref "Q7") (pin "1") (pinfunction "B_1") (pintype "passive"))
      (node (ref "R66") (pin "2") (pinfunction "2_2") (pintype "passive"))
    )
    (net (code "24") (name "Net-(Q7-C)") (class "Default")
      (node (ref "Q7") (pin "3") (pinfunction "C_3") (pintype "passive"))
      (node (ref "R60") (pin "1") (pinfunction "1_1") (pintype "passive"))
      (node (ref "R64") (pin "2") (pinfunction "2_2") (pintype "passive"))
      (node (ref "U16") (pin "1") (pinfunction "G2_1") (pintype "passive"))
    )
    (net (code "25") (name "Net-(Q8-B)") (class "Default")
      (node (ref "Q8") (pin "1") (pinfunction "B_1") (pintype "passive"))
      (node (ref "R72") (pin "2") (pinfunction "2_2") (pintype "passive"))
    )
    (net (code "26") (name "Net-(Q8-C)") (class "Default")
      (node (ref "Q8") (pin "3") (pinfunction "C_3") (pintype "passive"))
      (node (ref "R54") (pin "1") (pinfunction "1_1") (pintype "passive"))
      (node (ref "R65") (pin "2") (pinfunction "2_2") (pintype "passive"))
      (node (ref "U13") (pin "1") (pinfunction "G2_1") (pintype "passive"))
    )
    (net (code "27") (name "Net-(Q9-B)") (class "Default")
      (node (ref "Q9") (pin "1") (pinfunction "B_1") (pintype "passive"))
      (node (ref "R73") (pin "2") (pinfunction "2_2") (pintype "passive"))
    )
    (net (code "28") (name "Net-(Q9-C)") (class "Default")
      (node (ref "Q9") (pin "3") (pinfunction "C_3") (pintype "passive"))
      (node (ref "R55") (pin "1") (pinfunction "1_1") (pintype "passive"))
      (node (ref "U13") (pin "3") (pinfunction "G1_3") (pintype "passive"))
    )
    (net (code "29") (name "Net-(Q10-B)") (class "Default")
      (node (ref "Q10") (pin "1") (pinfunction "B_1") (pintype "passive"))
      (node (ref "R69") (pin "2") (pinfunction "2_2") (pintype "passive"))
    )
    (net (code "30") (name "Net-(Q10-C)") (class "Default")
      (node (ref "Q10") (pin "3") (pinfunction "C_3") (pintype "passive"))
      (node (ref "R57") (pin "1") (pinfunction "1_1") (pintype "passive"))
      (node (ref "U14") (pin "3") (pinfunction "G1_3") (pintype "passive"))
    )
    (net (code "31") (name "Net-(Q11-B)") (class "Default")
      (node (ref "Q11") (pin "1") (pinfunction "B_1") (pintype "passive"))
      (node (ref "R70") (pin "2") (pinfunction "2_2") (pintype "passive"))
    )
    (net (code "32") (name "Net-(Q11-C)") (class "Default")
      (node (ref "Q11") (pin "3") (pinfunction "C_3") (pintype "passive"))
      (node (ref "R58") (pin "1") (pinfunction "1_1") (pintype "passive"))
      (node (ref "R63") (pin "2") (pinfunction "2_2") (pintype "passive"))
      (node (ref "U15") (pin "1") (pinfunction "G2_1") (pintype "passive"))
    )
    (net (code "33") (name "Net-(Q12-B)") (class "Default")
      (node (ref "Q12") (pin "1") (pinfunction "B_1") (pintype "passive"))
      (node (ref "R68") (pin "2") (pinfunction "2_2") (pintype "passive"))
    )
    (net (code "34") (name "Net-(Q12-C)") (class "Default")
      (node (ref "Q12") (pin "3") (pinfunction "C_3") (pintype "passive"))
      (node (ref "R56") (pin "1") (pinfunction "1_1") (pintype "passive"))
      (node (ref "R62") (pin "2") (pinfunction "2_2") (pintype "passive"))
      (node (ref "U14") (pin "1") (pinfunction "G2_1") (pintype "passive"))
    )
    (net (code "35") (name "Net-(Q13-B)") (class "Default")
      (node (ref "Q13") (pin "1") (pinfunction "B_1") (pintype "passive"))
      (node (ref "R71") (pin "2") (pinfunction "2_2") (pintype "passive"))
    )
    (net (code "36") (name "Net-(Q13-C)") (class "Default")
      (node (ref "Q13") (pin "3") (pinfunction "C_3") (pintype "passive"))
      (node (ref "R59") (pin "1") (pinfunction "1_1") (pintype "passive"))
      (node (ref "U15") (pin "3") (pinfunction "G1_3") (pintype "passive"))
    )
    (net (code "37") (name "Net-(Q14-B)") (class "Default")
      (node (ref "Q14") (pin "1") (pinfunction "B_1") (pintype "passive"))
      (node (ref "R80") (pin "1") (pinfunction "1_1") (pintype "passive"))
    )
    (net (code "38") (name "Net-(Q14-C)") (class "Default")
      (node (ref "Q14") (pin "3") (pinfunction "C_3") (pintype "passive"))
      (node (ref "R77") (pin "1") (pinfunction "1_1") (pintype "passive"))
      (node (ref "U19") (pin "3") (pinfunction "G1_3") (pintype "passive"))
    )
    (net (code "39") (name "Net-(R79-Pad1)") (class "Default")
      (node (ref "R79") (pin "1") (pinfunction "1_1") (pintype "passive"))
      (node (ref "R82") (pin "1") (pinfunction "1_1") (pintype "passive"))
      (node (ref "R84") (pin "2") (pinfunction "2_2") (pintype "passive"))
    )
    (net (code "40") (name "Net-(U11-RA0{slash}ICSPDAT)") (class "Default")
      (node (ref "J5") (pin "3") (pinfunction "3_3") (pintype "passive"))
      (node (ref "U11") (pin "19") (pinfunction "RA0/ICSPDAT_19") (pintype "passive"))
    )
    (net (code "41") (name "Net-(U11-RA1{slash}ICSPCLK)") (class "Default")
      (node (ref "J5") (pin "2") (pinfunction "2_2") (pintype "passive"))
      (node (ref "U11") (pin "18") (pinfunction "RA1/ICSPCLK_18") (pintype "passive"))
    )
    (net (code "42") (name "Net-(U11-RA4)") (class "Default")
      (node (ref "R50") (pin "2") (pinfunction "2_2") (pintype "passive"))
      (node (ref "U11") (pin "3") (pinfunction "RA4_3") (pintype "passive"))
    )
    (net (code "43") (name "Net-(U11-RB5)") (class "Default")
      (node (ref "R53") (pin "2") (pinfunction "2_2") (pintype "passive"))
      (node (ref "U11") (pin "12") (pinfunction "RB5_12") (pintype "passive"))
    )
    (net (code "44") (name "Net-(U13-D1)") (class "Default")
      (node (ref "C23") (pin "1") (pinfunction "1_1") (pintype "passive"))
      (node (ref "J6") (pin "2") (pinfunction "2_2") (pintype "passive"))
      (node (ref "U13") (pin "4") (pinfunction "D1_4") (pintype "passive"))
      (node (ref "U13") (pin "6") (pinfunction "D2_6") (pintype "passive"))
    )
    (net (code "45") (name "Net-(U14-D1)") (class "Default")
      (node (ref "C23") (pin "2") (pinfunction "2_2") (pintype "passive"))
      (node (ref "J6") (pin "1") (pinfunction "1_1") (pintype "passive"))
      (node (ref "U14") (pin "4") (pinfunction "D1_4") (pintype "passive"))
      (node (ref "U14") (pin "6") (pinfunction "D2_6") (pintype "passive"))
    )
    (net (code "46") (name "Net-(U15-D1)") (class "Default")
      (node (ref "C24") (pin "1") (pinfunction "1_1") (pintype "passive"))
      (node (ref "J7") (pin "2") (pinfunction "2_2") (pintype "passive"))
      (node (ref "U15") (pin "4") (pinfunction "D1_4") (pintype "passive"))
      (node (ref "U15") (pin "6") (pinfunction "D2_6") (pintype "passive"))
    )
    (net (code "47") (name "Net-(U16-D1)") (class "Default")
      (node (ref "C24") (pin "2") (pinfunction "2_2") (pintype "passive"))
      (node (ref "J7") (pin "1") (pinfunction "1_1") (pintype "passive"))
      (node (ref "U16") (pin "4") (pinfunction "D1_4") (pintype "passive"))
      (node (ref "U16") (pin "6") (pinfunction "D2_6") (pintype "passive"))
    )
    (net (code "48") (name "Net-(U17-PROG)") (class "Default")
      (node (ref "R74") (pin "2") (pinfunction "2_2") (pintype "passive"))
      (node (ref "U17") (pin "5") (pinfunction "PROG_5") (pintype "passive"))
    )
    (net (code "49") (name "Net-(U19-D2)") (class "Default")
      (node (ref "R85") (pin "1") (pinfunction "1_1") (pintype "passive"))
      (node (ref "R86") (pin "1") (pinfunction "1_1") (pintype "passive"))
      (node (ref "U19") (pin "6") (pinfunction "D2_6") (pintype "passive"))
    )
    (net (code "50") (name "Net-(U19-G2)") (class "Default")
      (node (ref "R78") (pin "1") (pinfunction "1_1") (pintype "passive"))
      (node (ref "R81") (pin "2") (pinfunction "2_2") (pintype "passive"))
      (node (ref "U19") (pin "1") (pinfunction "G2_1") (pintype "passive"))
    )
    (net (code "51") (name "VCC") (class "Default")
      (node (ref "C22") (pin "2") (pinfunction "2_2") (pintype "passive"))
      (node (ref "C27") (pin "2") (pinfunction "2_2") (pintype "passive"))
      (node (ref "D9") (pin "1") (pinfunction "A_1") (pintype "passive"))
      (node (ref "J5") (pin "5") (pinfunction "5_5") (pintype "passive"))
      (node (ref "R47") (pin "2") (pinfunction "2_2") (pintype "passive"))
      (node (ref "R48") (pin "2") (pinfunction "2_2") (pintype "passive"))
      (node (ref "R52") (pin "2") (pinfunction "2_2") (pintype "passive"))
      (node (ref "R85") (pin "2") (pinfunction "2_2") (pintype "passive"))
      (node (ref "TP6") (pin "1") (pinfunction "1_1") (pintype "passive"))
      (node (ref "U11") (pin "1") (pinfunction "VDD_1") (pintype "passive"))
      (node (ref "U18") (pin "3") (pinfunction "VOUT_3") (pintype "passive"))
    )
    (net (code "52") (name "VCC_BATT") (class "Default")
      (node (ref "C25") (pin "2") (pinfunction "2_2") (pintype "passive"))
      (node (ref "J8") (pin "1") (pinfunction "1_1") (pintype "passive"))
      (node (ref "R77") (pin "2") (pinfunction "2_2") (pintype "passive"))
      (node (ref "SW1") (pin "3") (pinfunction "3_3") (pintype "passive"))
      (node (ref "SW1") (pin "4") (pinfunction "4_4") (pintype "passive"))
      (node (ref "SW1") (pin "7") (pinfunction "7_7") (pintype "passive"))
      (node (ref "SW1") (pin "8") (pinfunction "8_8") (pintype "passive"))
      (node (ref "TP1") (pin "1") (pinfunction "1_1") (pintype "passive"))
      (node (ref "U17") (pin "3") (pinfunction "Vbat_3") (pintype "passive"))
      (node (ref "U19") (pin "2") (pinfunction "S1_2") (pintype "passive"))
    )
    (net (code "53") (name "Vdc") (class "Default")
      (node (ref "C28") (pin "2") (pinfunction "2_2") (pintype "passive"))
      (node (ref "R54") (pin "2") (pinfunction "2_2") (pintype "passive"))
      (node (ref "R55") (pin "2") (pinfunction "2_2") (pintype "passive"))
      (node (ref "R56") (pin "2") (pinfunction "2_2") (pintype "passive"))
      (node (ref "R57") (pin "2") (pinfunction "2_2") (pintype "passive"))
      (node (ref "R58") (pin "2") (pinfunction "2_2") (pintype "passive"))
      (node (ref "R59") (pin "2") (pinfunction "2_2") (pintype "passive"))
      (node (ref "R60") (pin "2") (pinfunction "2_2") (pintype "passive"))
      (node (ref "R61") (pin "2") (pinfunction "2_2") (pintype "passive"))
      (node (ref "R79") (pin "2") (pinfunction "2_2") (pintype "passive"))
      (node (ref "SW1") (pin "1") (pinfunction "1_1") (pintype "passive"))
      (node (ref "SW1") (pin "2") (pinfunction "2_2") (pintype "passive"))
      (node (ref "SW1") (pin "5") (pinfunction "5_5") (pintype "passive"))
      (node (ref "SW1") (pin "6") (pinfunction "6_6") (pintype "passive"))
      (node (ref "TP5") (pin "1") (pinfunction "1_1") (pintype "passive"))
      (node (ref "U13") (pin "2") (pinfunction "S1_2") (pintype "passive"))
      (node (ref "U14") (pin "2") (pinfunction "S1_2") (pintype "passive"))
      (node (ref "U15") (pin "2") (pinfunction "S1_2") (pintype "passive"))
      (node (ref "U16") (pin "2") (pinfunction "S1_2") (pintype "passive"))
      (node (ref "U18") (pin "1") (pinfunction "VIN_1") (pintype "passive"))
      (node (ref "U19") (pin "4") (pinfunction "D1_4") (pintype "passive"))
    )
    (net (code "54") (name "unconnected-(U11-RB7-Pad10)") (class "Default")
      (node (ref "U11") (pin "10") (pinfunction "RB7_10") (pintype "passive+no_connect"))
    )
    (net (code "55") (name "unconnected-(U11-RC5-Pad5)") (class "Default")
      (node (ref "U11") (pin "5") (pinfunction "RC5_5") (pintype "passive+no_connect"))
    )
    (net (code "56") (name "unconnected-(U11-RC7-Pad9)") (class "Default")
      (node (ref "U11") (pin "9") (pinfunction "RC7_9") (pintype "passive+no_connect"))
    )
  )
)
